# design.net
KiCad netlist of a schematic drawn in Altium Designer
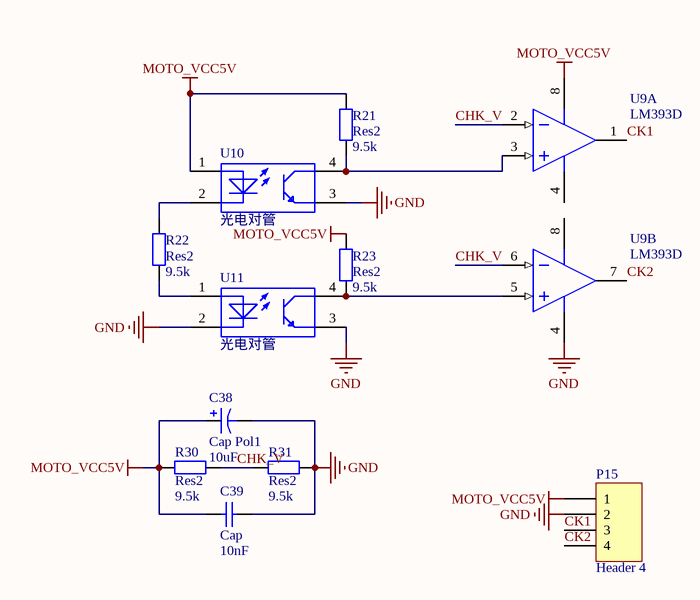
[diagram p0: 电机码盘.SchDoc]

(export (version "E")
  (design (tool "Eeschema 10.0.6"))
  (components
    (comp (ref "C38")
      (value "Cap Pol1")
      (footprint "LC-1210_C")
      (description "Polarized Capacitor (Radial)")
      (fields (field (name "ALTIUM_VALUE") "10uF") (field (name "PUBLISHER") "Altium Limited"))
      (libsource (lib "Miscellaneous Devices") (part "Cap Pol1"))
    )
    (comp (ref "C39")
      (value "Cap")
      (footprint "LC-0603_C")
      (description "Capacitor")
      (fields (field (name "ALTIUM_VALUE") "10nF") (field (name "PUBLISHER") "Altium Limited"))
      (libsource (lib "Miscellaneous Devices") (part "Cap"))
    )
    (comp (ref "P15")
      (value "Header 4")
      (footprint "HDR1X4")
      (description "Header, 4-Pin")
      (fields (field (name "PUBLISHER") "Altium Limited"))
      (libsource (lib "Miscellaneous Connectors") (part "Header 4"))
    )
    (comp (ref "R21")
      (value "Res2")
      (footprint "LC-0603_R")
      (description "Resistor")
      (fields (field (name "ALTIUM_VALUE") "9.5k") (field (name "PUBLISHER") "Altium Limited"))
      (libsource (lib "Miscellaneous Devices") (part "Res2"))
    )
    (comp (ref "R22")
      (value "Res2")
      (footprint "LC-0603_R")
      (description "Resistor")
      (fields (field (name "ALTIUM_VALUE") "9.5k") (field (name "PUBLISHER") "Altium Limited"))
      (libsource (lib "Miscellaneous Devices") (part "Res2"))
    )
    (comp (ref "R23")
      (value "Res2")
      (footprint "LC-0603_R")
      (description "Resistor")
      (fields (field (name "ALTIUM_VALUE") "9.5k") (field (name "PUBLISHER") "Altium Limited"))
      (libsource (lib "Miscellaneous Devices") (part "Res2"))
    )
    (comp (ref "R30")
      (value "Res2")
      (footprint "LC-0603_R")
      (description "Resistor")
      (fields (field (name "ALTIUM_VALUE") "9.5k") (field (name "PUBLISHER") "Altium Limited"))
      (libsource (lib "") (part "Res2_1"))
    )
    (comp (ref "R31")
      (value "Res2")
      (footprint "LC-0603_R")
      (description "Resistor")
      (fields (field (name "ALTIUM_VALUE") "9.5k") (field (name "PUBLISHER") "Altium Limited"))
      (libsource (lib "") (part "Res2_1"))
    )
    (comp (ref "U9")
      (value "LM393D")
      (footprint "SO8_N")
      (description "Low-Power Dual Voltage Comparator")
      (fields (field (name "PUBLISHER") "Altium Limited"))
      (libsource (lib "ST Analog Comparator") (part "LM393D"))
    )
    (comp (ref "U10") (value "光电对管") (footprint "马达光电对管") (libsource (lib "ROS_CAR_LIB") (part "光电对管")))
    (comp (ref "U11") (value "光电对管") (footprint "马达光电对管") (libsource (lib "ROS_CAR_LIB") (part "光电对管")))
  )
  (nets
    (net (code "1") (name "/CHK_V") (class "Default")
      (node (ref "R30") (pin "2") (pinfunction "2_2") (pintype "passive"))
      (node (ref "R31") (pin "1") (pinfunction "1_1") (pintype "passive"))
      (node (ref "U9") (pin "2") (pinfunction "IN-_2") (pintype "input"))
      (node (ref "U9") (pin "6") (pinfunction "IN-_6") (pintype "input"))
    )
    (net (code "2") (name "/CK1") (class "Default")
      (node (ref "P15") (pin "3") (pinfunction "3_3") (pintype "passive"))
      (node (ref "U9") (pin "1") (pinfunction "OUT_1") (pintype "open_collector"))
    )
    (net (code "3") (name "/CK2") (class "Default")
      (node (ref "P15") (pin "4") (pinfunction "4_4") (pintype "passive"))
      (node (ref "U9") (pin "7") (pinfunction "OUT_7") (pintype "open_collector"))
    )
    (net (code "4") (name "GND") (class "Default")
      (node (ref "C38") (pin "2") (pinfunction "2_2") (pintype "passive"))
      (node (ref "C39") (pin "2") (pinfunction "2_2") (pintype "passive"))
      (node (ref "P15") (pin "2") (pinfunction "2_2") (pintype "passive"))
      (node (ref "R31") (pin "2") (pinfunction "2_2") (pintype "passive"))
      (node (ref "U10") (pin "3") (pinfunction "3_3") (pintype "passive"))
      (node (ref "U11") (pin "2") (pinfunction "2_2") (pintype "passive"))
      (node (ref "U11") (pin "3") (pinfunction "3_3") (pintype "passive"))
      (node (ref "U9") (pin "4") (pinfunction "V-_4") (pintype "power_in"))
    )
    (net (code "5") (name "MOTO_VCC5V") (class "Default")
      (node (ref "C38") (pin "1") (pinfunction "1_1") (pintype "passive"))
      (node (ref "C39") (pin "1") (pinfunction "1_1") (pintype "passive"))
      (node (ref "P15") (pin "1") (pinfunction "1_1") (pintype "passive"))
      (node (ref "R21") (pin "1") (pinfunction "1_1") (pintype "passive"))
      (node (ref "R23") (pin "1") (pinfunction "1_1") (pintype "passive"))
      (node (ref "R30") (pin "1") (pinfunction "1_1") (pintype "passive"))
      (node (ref "U10") (pin "1") (pinfunction "1_1") (pintype "passive"))
      (node (ref "U9") (pin "8") (pinfunction "V+_8") (pintype "power_in"))
    )
    (net (code "6") (name "Net-(R22-Pad1)") (class "Default")
      (node (ref "R22") (pin "1") (pinfunction "1_1") (pintype "passive"))
      (node (ref "U10") (pin "2") (pinfunction "2_2") (pintype "passive"))
    )
    (net (code "7") (name "Net-(R22-Pad2)") (class "Default")
      (node (ref "R22") (pin "2") (pinfunction "2_2") (pintype "passive"))
      (node (ref "U11") (pin "1") (pinfunction "1_1") (pintype "passive"))
    )
    (net (code "8") (name "Net-(U9A-IN+)") (class "Default")
      (node (ref "R21") (pin "2") (pinfunction "2_2") (pintype "passive"))
      (node (ref "U10") (pin "4") (pinfunction "4_4") (pintype "passive"))
      (node (ref "U9") (pin "3") (pinfunction "IN+_3") (pintype "input"))
    )
    (net (code "9") (name "Net-(U9B-IN+)") (class "Default")
      (node (ref "R23") (pin "2") (pinfunction "2_2") (pintype "passive"))
      (node (ref "U11") (pin "4") (pinfunction "4_4") (pintype "passive"))
      (node (ref "U9") (pin "5") (pinfunction "IN+_5") (pintype "input"))
    )
    (net (code "10") (name "unconnected-(U9A-V--Pad4)") (class "Default")
      (node (ref "U9") (pin "4") (pinfunction "V-_4") (pintype "power_in"))
    )
    (net (code "11") (name "unconnected-(U9B-V+-Pad8)") (class "Default")
      (node (ref "U9") (pin "8") (pinfunction "V+_8") (pintype "power_in"))
    )
  )
)
